# Ethernet_DP.net
KiCad netlist of a schematic drawn in Altium Designer
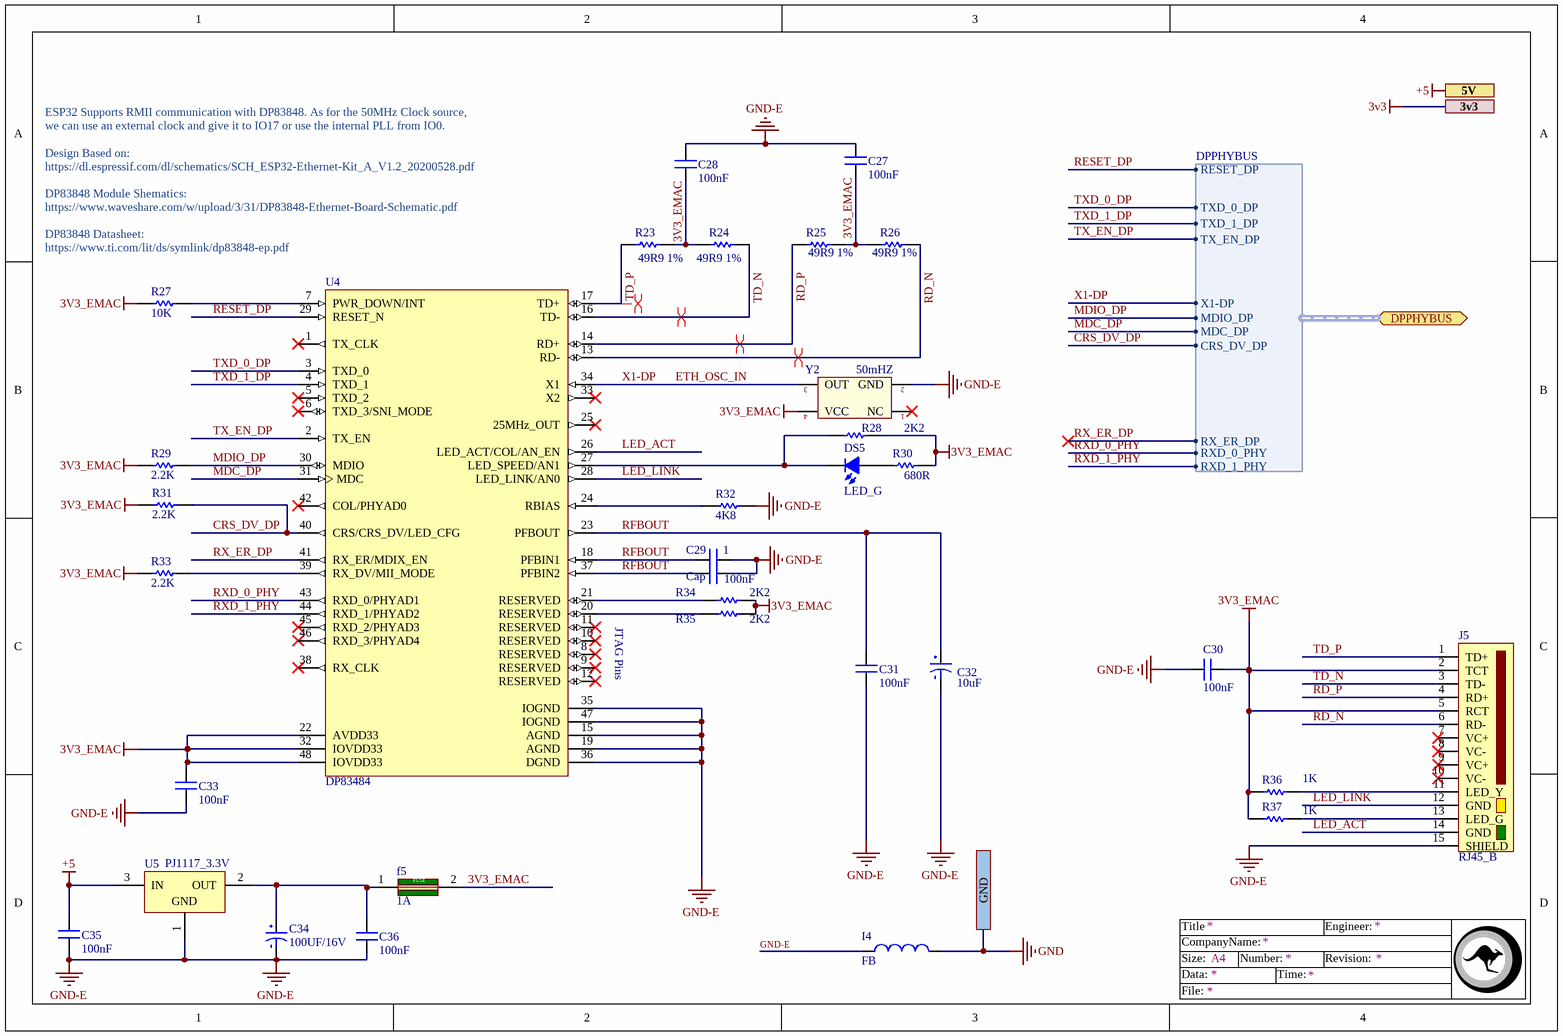
[diagram p0: Ethernet DP.SchDoc]

(export (version "E")
  (design (tool "Eeschema 10.0.6"))
  (components
    (comp (ref "1")
      (value "Cap")
      (footprint "Cap0805")
      (description "Surface mount Capacitor")
      (libsource (lib "PMLIB2020-V3") (part "Cap"))
    )
    (comp (ref "C27")
      (value "100nF")
      (footprint "Cap0805")
      (description "Surface mount Capacitor")
      (libsource (lib "PMLIB2020-V3") (part "Cap"))
    )
    (comp (ref "C28")
      (value "100nF")
      (footprint "Cap0805")
      (description "Surface mount Capacitor")
      (libsource (lib "PMLIB2020-V3") (part "Cap"))
    )
    (comp (ref "C29")
      (value "100nF")
      (footprint "Cap0805")
      (description "Surface mount Capacitor")
      (libsource (lib "PMLIB2020-V3") (part "Cap"))
    )
    (comp (ref "C30")
      (value "100nF")
      (footprint "Cap0805")
      (description "Surface mount Capacitor")
      (libsource (lib "PMLIB2020-V3") (part "Cap"))
    )
    (comp (ref "C31")
      (value "100nF")
      (footprint "Cap0805")
      (description "Surface mount Capacitor")
      (libsource (lib "PMLIB2020-V3") (part "Cap"))
    )
    (comp (ref "C32")
      (value "10uF")
      (footprint "CAPMOL_B")
      (description "Polarity")
      (libsource (lib "PMLIB2020-V3") (part "Cap_P"))
    )
    (comp (ref "C33")
      (value "100nF")
      (footprint "Cap0805")
      (description "Surface mount Capacitor")
      (libsource (lib "PMLIB2020-V3") (part "Cap"))
    )
    (comp (ref "C34")
      (value "100UF/16V")
      (footprint "CAPMOL_A")
      (description "Polarity")
      (libsource (lib "PMLIB2020-V3") (part "Cap_P"))
    )
    (comp (ref "C35")
      (value "100nF")
      (footprint "Cap0805")
      (description "Surface mount Capacitor")
      (libsource (lib "PMLIB2020-V3") (part "Cap"))
    )
    (comp (ref "C36")
      (value "100nF")
      (footprint "Cap0805")
      (description "Surface mount Capacitor")
      (libsource (lib "PMLIB2020-V3") (part "Cap"))
    )
    (comp (ref "DS5")
      (value "LED_G")
      (footprint "LED_0805Green")
      (description "LED")
      (libsource (lib "PMLIB2020-V3") (part "LED"))
    )
    (comp (ref "f5")
      (value "1A")
      (footprint "1206")
      (description "Fuse")
      (libsource (lib "PMLIB2020-V3") (part "Fuse"))
    )
    (comp (ref "I4")
      (value "FB")
      (footprint "1206")
      (description "Indicator")
      (libsource (lib "PMLIB2020-V3") (part "Inductor"))
    )
    (comp (ref "J5")
      (value "RJ45_B")
      (footprint "RJ45_B")
      (description "Ethernet Connector")
      (libsource (lib "PMLIB2020-V3") (part "RJ45_B"))
    )
    (comp (ref "R23")
      (value "49R9 1%")
      (footprint "R0805")
      (description "Resistor")
      (libsource (lib "PMLIB2020-V3") (part "Resistor"))
    )
    (comp (ref "R24")
      (value "49R9 1%")
      (footprint "R0805")
      (description "Resistor")
      (libsource (lib "PMLIB2020-V3") (part "Resistor"))
    )
    (comp (ref "R25")
      (value "49R9 1%")
      (footprint "R0805")
      (description "Resistor")
      (libsource (lib "PMLIB2020-V3") (part "Resistor"))
    )
    (comp (ref "R26")
      (value "49R9 1%")
      (footprint "R0805")
      (description "Resistor")
      (libsource (lib "PMLIB2020-V3") (part "Resistor"))
    )
    (comp (ref "R27")
      (value "10K")
      (footprint "R0805")
      (description "Resistor")
      (libsource (lib "PMLIB2020-V3") (part "Resistor"))
    )
    (comp (ref "R28")
      (value "2K2")
      (footprint "R0805")
      (description "Resistor")
      (libsource (lib "PMLIB2020-V3") (part "Resistor"))
    )
    (comp (ref "R29")
      (value "2.2K")
      (footprint "R0805")
      (description "Resistor")
      (libsource (lib "PMLIB2020-V3") (part "Resistor"))
    )
    (comp (ref "R30")
      (value "680R")
      (footprint "R0805")
      (description "Resistor")
      (libsource (lib "PMLIB2020-V3") (part "Resistor"))
    )
    (comp (ref "R31")
      (value "2.2K")
      (footprint "R0805")
      (description "Resistor")
      (libsource (lib "PMLIB2020-V3") (part "Resistor"))
    )
    (comp (ref "R32")
      (value "4K8")
      (footprint "R0805")
      (description "Resistor")
      (libsource (lib "PMLIB2020-V3") (part "Resistor"))
    )
    (comp (ref "R33")
      (value "2.2K")
      (footprint "R0805")
      (description "Resistor")
      (libsource (lib "PMLIB2020-V3") (part "Resistor"))
    )
    (comp (ref "R34")
      (value "2K2")
      (footprint "R0805")
      (description "Resistor")
      (libsource (lib "PMLIB2020-V3") (part "Resistor"))
    )
    (comp (ref "R35")
      (value "2K2")
      (footprint "R0805")
      (description "Resistor")
      (libsource (lib "PMLIB2020-V3") (part "Resistor"))
    )
    (comp (ref "R36")
      (value "1K")
      (footprint "R0805")
      (description "Resistor")
      (libsource (lib "PMLIB2020-V3") (part "Resistor"))
    )
    (comp (ref "R37")
      (value "1K")
      (footprint "R0805")
      (description "Resistor")
      (libsource (lib "PMLIB2020-V3") (part "Resistor"))
    )
    (comp (ref "U4")
      (value "DP83484")
      (footprint "DP83484")
      (description "Ethernet PHY")
      (libsource (lib "PMLIB2020-V3") (part "DP83484"))
    )
    (comp (ref "U5")
      (value "PJ1117_3.3V")
      (footprint "PJ1117s")
      (description "Regulator")
      (libsource (lib "PMLIB2020-V3") (part "PJ1117_3.3V"))
    )
    (comp (ref "Y2")
      (value "50mHZ")
      (footprint "Crystall 50Mhz")
      (description "Oscillator")
      (libsource (lib "PMLIB2020-V3") (part "Oscillator"))
    )
  )
  (nets
    (net (code "2") (name "+5") (class "Default")
      (node (ref "C35") (pin "2") (pinfunction "2_2") (pintype "passive"))
      (node (ref "U5") (pin "3") (pinfunction "IN_3") (pintype "power_in"))
    )
    (net (code "3") (name "/CRS_DV_DP") (class "Default")
      (node (ref "R31") (pin "1") (pinfunction "1_1") (pintype "passive"))
      (node (ref "U4") (pin "40") (pinfunction "CRS/CRS_DV/LED_CFG_40") (pintype "output"))
    )
    (net (code "4") (name "/ETH_OSC_IN") (class "Default")
      (node (ref "U4") (pin "34") (pinfunction "X1_34") (pintype "input"))
      (node (ref "Y2") (pin "3") (pinfunction "OUT_3") (pintype "passive"))
    )
    (net (code "5") (name "/LED_ACT") (class "Default")
      (node (ref "J5") (pin "14") (pinfunction "GND_14") (pintype "passive"))
      (node (ref "U4") (pin "26") (pinfunction "LED_ACT/COL/AN_EN_26") (pintype "output"))
    )
    (net (code "6") (name "/LED_LINK") (class "Default")
      (node (ref "J5") (pin "12") (pinfunction "GND_12") (pintype "passive"))
      (node (ref "U4") (pin "28") (pinfunction "LED_LINK/AN0_28") (pintype "output"))
    )
    (net (code "7") (name "/MDC_DP") (class "Default")
      (node (ref "U4") (pin "31") (pinfunction "MDC_31") (pintype "input"))
    )
    (net (code "8") (name "/MDIO_DP") (class "Default")
      (node (ref "R29") (pin "1") (pinfunction "1_1") (pintype "passive"))
      (node (ref "U4") (pin "30") (pinfunction "MDIO_30") (pintype "bidirectional"))
    )
    (net (code "9") (name "/RD_N") (class "Default")
      (node (ref "J5") (pin "6") (pinfunction "RD-_6") (pintype "passive"))
      (node (ref "R26") (pin "1") (pinfunction "1_1") (pintype "passive"))
      (node (ref "U4") (pin "13") (pinfunction "RD-_13") (pintype "bidirectional"))
    )
    (net (code "10") (name "/RD_P") (class "Default")
      (node (ref "J5") (pin "4") (pinfunction "RD+_4") (pintype "passive"))
      (node (ref "R25") (pin "2") (pinfunction "2_2") (pintype "passive"))
      (node (ref "U4") (pin "14") (pinfunction "RD+_14") (pintype "bidirectional"))
    )
    (net (code "11") (name "/RESET_DP") (class "Default")
      (node (ref "U4") (pin "29") (pinfunction "RESET_N_29") (pintype "input"))
    )
    (net (code "12") (name "/RFBOUT") (class "Default")
      (node (ref "1") (pin "1") (pinfunction "1_1") (pintype "passive"))
      (node (ref "C29") (pin "1") (pinfunction "1_1") (pintype "passive"))
      (node (ref "C31") (pin "2") (pinfunction "2_2") (pintype "passive"))
      (node (ref "C32") (pin "2") (pinfunction "2_2") (pintype "passive"))
      (node (ref "U4") (pin "18") (pinfunction "PFBIN1_18") (pintype "input"))
      (node (ref "U4") (pin "23") (pinfunction "PFBOUT_23") (pintype "output"))
      (node (ref "U4") (pin "37") (pinfunction "PFBIN2_37") (pintype "input"))
    )
    (net (code "13") (name "/RXD_0_PHY") (class "Default")
      (node (ref "U4") (pin "43") (pinfunction "RXD_0/PHYAD1_43") (pintype "output"))
    )
    (net (code "14") (name "/RXD_1_PHY") (class "Default")
      (node (ref "U4") (pin "44") (pinfunction "RXD_1/PHYAD2_44") (pintype "output"))
    )
    (net (code "15") (name "/RX_ER_DP") (class "Default")
      (node (ref "U4") (pin "41") (pinfunction "RX_ER/MDIX_EN_41") (pintype "output"))
    )
    (net (code "16") (name "/TD_N") (class "Default")
      (node (ref "J5") (pin "3") (pinfunction "TD-_3") (pintype "passive"))
      (node (ref "R24") (pin "1") (pinfunction "1_1") (pintype "passive"))
      (node (ref "U4") (pin "16") (pinfunction "TD-_16") (pintype "bidirectional"))
    )
    (net (code "17") (name "/TD_P") (class "Default")
      (node (ref "J5") (pin "1") (pinfunction "TD+_1") (pintype "passive"))
      (node (ref "R23") (pin "2") (pinfunction "2_2") (pintype "passive"))
      (node (ref "U4") (pin "17") (pinfunction "TD+_17") (pintype "bidirectional"))
    )
    (net (code "18") (name "/TXD_0_DP") (class "Default")
      (node (ref "U4") (pin "3") (pinfunction "TXD_0_3") (pintype "input"))
    )
    (net (code "19") (name "/TXD_1_DP") (class "Default")
      (node (ref "U4") (pin "4") (pinfunction "TXD_1_4") (pintype "input"))
    )
    (net (code "20") (name "/TX_EN_DP") (class "Default")
      (node (ref "U4") (pin "2") (pinfunction "TX_EN_2") (pintype "input"))
    )
    (net (code "22") (name "3V3_EMAC") (class "Default")
      (node (ref "C27") (pin "1") (pinfunction "1_1") (pintype "passive"))
      (node (ref "C28") (pin "1") (pinfunction "1_1") (pintype "passive"))
      (node (ref "C30") (pin "2") (pinfunction "2_2") (pintype "passive"))
      (node (ref "C33") (pin "1") (pinfunction "1_1") (pintype "passive"))
      (node (ref "J5") (pin "2") (pinfunction "TCT_2") (pintype "passive"))
      (node (ref "J5") (pin "5") (pinfunction "RCT_5") (pintype "passive"))
      (node (ref "R23") (pin "1") (pinfunction "1_1") (pintype "passive"))
      (node (ref "R24") (pin "2") (pinfunction "2_2") (pintype "passive"))
      (node (ref "R25") (pin "1") (pinfunction "1_1") (pintype "passive"))
      (node (ref "R26") (pin "2") (pinfunction "2_2") (pintype "passive"))
      (node (ref "R27") (pin "2") (pinfunction "2_2") (pintype "passive"))
      (node (ref "R28") (pin "1") (pinfunction "1_1") (pintype "passive"))
      (node (ref "R29") (pin "2") (pinfunction "2_2") (pintype "passive"))
      (node (ref "R30") (pin "1") (pinfunction "1_1") (pintype "passive"))
      (node (ref "R31") (pin "2") (pinfunction "2_2") (pintype "passive"))
      (node (ref "R33") (pin "2") (pinfunction "2_2") (pintype "passive"))
      (node (ref "R34") (pin "1") (pinfunction "1_1") (pintype "passive"))
      (node (ref "R35") (pin "1") (pinfunction "1_1") (pintype "passive"))
      (node (ref "R36") (pin "2") (pinfunction "2_2") (pintype "passive"))
      (node (ref "R37") (pin "2") (pinfunction "2_2") (pintype "passive"))
      (node (ref "U4") (pin "22") (pinfunction "AVDD33_22") (pintype "power_in"))
      (node (ref "U4") (pin "32") (pinfunction "IOVDD33_32") (pintype "power_in"))
      (node (ref "U4") (pin "48") (pinfunction "IOVDD33_48") (pintype "power_in"))
      (node (ref "Y2") (pin "4") (pinfunction "VCC_4") (pintype "passive"))
      (node (ref "f5") (pin "2") (pinfunction "OUT_2") (pintype "passive"))
    )
    (net (code "24") (name "GND") (class "Default")
      (node (ref "I4") (pin "2") (pinfunction "2_2") (pintype "passive"))
    )
    (net (code "25") (name "GND-E") (class "Default")
      (node (ref "1") (pin "2") (pinfunction "2_2") (pintype "passive"))
      (node (ref "C27") (pin "2") (pinfunction "2_2") (pintype "passive"))
      (node (ref "C28") (pin "2") (pinfunction "2_2") (pintype "passive"))
      (node (ref "C29") (pin "2") (pinfunction "2_2") (pintype "passive"))
      (node (ref "C30") (pin "1") (pinfunction "1_1") (pintype "passive"))
      (node (ref "C31") (pin "1") (pinfunction "1_1") (pintype "passive"))
      (node (ref "C32") (pin "1") (pinfunction "1_1") (pintype "passive"))
      (node (ref "C33") (pin "2") (pinfunction "2_2") (pintype "passive"))
      (node (ref "C34") (pin "1") (pinfunction "1_1") (pintype "passive"))
      (node (ref "C35") (pin "1") (pinfunction "1_1") (pintype "passive"))
      (node (ref "C36") (pin "1") (pinfunction "1_1") (pintype "passive"))
      (node (ref "I4") (pin "1") (pinfunction "1_1") (pintype "passive"))
      (node (ref "J5") (pin "15") (pinfunction "SHIELD_15") (pintype "passive"))
      (node (ref "R32") (pin "1") (pinfunction "1_1") (pintype "passive"))
      (node (ref "U4") (pin "15") (pinfunction "AGND_15") (pintype "power_in"))
      (node (ref "U4") (pin "19") (pinfunction "AGND_19") (pintype "power_in"))
      (node (ref "U4") (pin "35") (pinfunction "IOGND_35") (pintype "power_in"))
      (node (ref "U4") (pin "36") (pinfunction "DGND_36") (pintype "power_in"))
      (node (ref "U4") (pin "47") (pinfunction "IOGND_47") (pintype "power_in"))
      (node (ref "U5") (pin "1") (pinfunction "GND_1") (pintype "power_in"))
      (node (ref "Y2") (pin "2") (pinfunction "GND_2") (pintype "passive"))
    )
    (net (code "26") (name "Net-(DS5-PadA)") (class "Default")
      (node (ref "DS5") (pin "A") (pinfunction "A_A") (pintype "passive"))
      (node (ref "R30") (pin "2") (pinfunction "2_2") (pintype "passive"))
    )
    (net (code "27") (name "Net-(J5-LED_G)") (class "Default")
      (node (ref "J5") (pin "13") (pinfunction "LED_G_13") (pintype "passive"))
      (node (ref "R37") (pin "1") (pinfunction "1_1") (pintype "passive"))
    )
    (net (code "28") (name "Net-(J5-LED_Y)") (class "Default")
      (node (ref "J5") (pin "11") (pinfunction "LED_Y_11") (pintype "passive"))
      (node (ref "R36") (pin "1") (pinfunction "1_1") (pintype "passive"))
    )
    (net (code "29") (name "Net-(R34-Pad2)") (class "Default")
      (node (ref "R34") (pin "2") (pinfunction "2_2") (pintype "passive"))
      (node (ref "U4") (pin "21") (pinfunction "RESERVED_21") (pintype "bidirectional"))
    )
    (net (code "30") (name "Net-(R35-Pad2)") (class "Default")
      (node (ref "R35") (pin "2") (pinfunction "2_2") (pintype "passive"))
      (node (ref "U4") (pin "20") (pinfunction "RESERVED_20") (pintype "bidirectional"))
    )
    (net (code "31") (name "Net-(U4-LED_SPEED{slash}AN1)") (class "Default")
      (node (ref "DS5") (pin "K") (pinfunction "K_K") (pintype "passive"))
      (node (ref "R28") (pin "2") (pinfunction "2_2") (pintype "passive"))
      (node (ref "U4") (pin "27") (pinfunction "LED_SPEED/AN1_27") (pintype "output"))
    )
    (net (code "32") (name "Net-(U4-PWR_DOWN{slash}INT)") (class "Default")
      (node (ref "R27") (pin "1") (pinfunction "1_1") (pintype "passive"))
      (node (ref "U4") (pin "7") (pinfunction "PWR_DOWN/INT_7") (pintype "input"))
    )
    (net (code "33") (name "Net-(U4-RBIAS)") (class "Default")
      (node (ref "R32") (pin "2") (pinfunction "2_2") (pintype "passive"))
      (node (ref "U4") (pin "24") (pinfunction "RBIAS_24") (pintype "input"))
    )
    (net (code "34") (name "Net-(U4-RX_DV{slash}MII_MODE)") (class "Default")
      (node (ref "R33") (pin "1") (pinfunction "1_1") (pintype "passive"))
      (node (ref "U4") (pin "39") (pinfunction "RX_DV/MII_MODE_39") (pintype "output"))
    )
    (net (code "35") (name "Net-(U5-OUT)") (class "Default")
      (node (ref "C34") (pin "2") (pinfunction "2_2") (pintype "passive"))
      (node (ref "C36") (pin "2") (pinfunction "2_2") (pintype "passive"))
      (node (ref "U5") (pin "2") (pinfunction "OUT_2") (pintype "power_in"))
      (node (ref "f5") (pin "1") (pinfunction "IN_1") (pintype "passive"))
    )
    (net (code "36") (name "unconnected-(J5-VC+-Pad7)") (class "Default")
      (node (ref "J5") (pin "7") (pinfunction "VC+_7") (pintype "passive+no_connect"))
    )
    (net (code "37") (name "unconnected-(J5-VC+-Pad9)") (class "Default")
      (node (ref "J5") (pin "9") (pinfunction "VC+_9") (pintype "passive+no_connect"))
    )
    (net (code "38") (name "unconnected-(J5-VC--Pad8)") (class "Default")
      (node (ref "J5") (pin "8") (pinfunction "VC-_8") (pintype "passive+no_connect"))
    )
    (net (code "39") (name "unconnected-(J5-VC--Pad10)") (class "Default")
      (node (ref "J5") (pin "10") (pinfunction "VC-_10") (pintype "passive+no_connect"))
    )
    (net (code "40") (name "unconnected-(U4-25MHz_OUT-Pad25)") (class "Default")
      (node (ref "U4") (pin "25") (pinfunction "25MHz_OUT_25") (pintype "output+no_connect"))
    )
    (net (code "41") (name "unconnected-(U4-COL{slash}PHYAD0-Pad42)") (class "Default")
      (node (ref "U4") (pin "42") (pinfunction "COL/PHYAD0_42") (pintype "output+no_connect"))
    )
    (net (code "42") (name "unconnected-(U4-RESERVED-Pad8)") (class "Default")
      (node (ref "U4") (pin "8") (pinfunction "RESERVED_8") (pintype "bidirectional+no_connect"))
    )
    (net (code "43") (name "unconnected-(U4-RESERVED-Pad9)") (class "Default")
      (node (ref "U4") (pin "9") (pinfunction "RESERVED_9") (pintype "bidirectional+no_connect"))
    )
    (net (code "44") (name "unconnected-(U4-RESERVED-Pad10)") (class "Default")
      (node (ref "U4") (pin "10") (pinfunction "RESERVED_10") (pintype "bidirectional+no_connect"))
    )
    (net (code "45") (name "unconnected-(U4-RESERVED-Pad11)") (class "Default")
      (node (ref "U4") (pin "11") (pinfunction "RESERVED_11") (pintype "bidirectional+no_connect"))
    )
    (net (code "46") (name "unconnected-(U4-RESERVED-Pad12)") (class "Default")
      (node (ref "U4") (pin "12") (pinfunction "RESERVED_12") (pintype "bidirectional+no_connect"))
    )
    (net (code "47") (name "unconnected-(U4-RXD_2{slash}PHYAD3-Pad45)") (class "Default")
      (node (ref "U4") (pin "45") (pinfunction "RXD_2/PHYAD3_45") (pintype "output+no_connect"))
    )
    (net (code "48") (name "unconnected-(U4-RXD_3{slash}PHYAD4-Pad46)") (class "Default")
      (node (ref "U4") (pin "46") (pinfunction "RXD_3/PHYAD4_46") (pintype "output+no_connect"))
    )
    (net (code "49") (name "unconnected-(U4-RX_CLK-Pad38)") (class "Default")
      (node (ref "U4") (pin "38") (pinfunction "RX_CLK_38") (pintype "output+no_connect"))
    )
    (net (code "50") (name "unconnected-(U4-TXD_2-Pad5)") (class "Default")
      (node (ref "U4") (pin "5") (pinfunction "TXD_2_5") (pintype "input+no_connect"))
    )
    (net (code "51") (name "unconnected-(U4-TXD_3{slash}SNI_MODE-Pad6)") (class "Default")
      (node (ref "U4") (pin "6") (pinfunction "TXD_3/SNI_MODE_6") (pintype "bidirectional+no_connect"))
    )
    (net (code "52") (name "unconnected-(U4-TX_CLK-Pad1)") (class "Default")
      (node (ref "U4") (pin "1") (pinfunction "TX_CLK_1") (pintype "output+no_connect"))
    )
    (net (code "53") (name "unconnected-(U4-X2-Pad33)") (class "Default")
      (node (ref "U4") (pin "33") (pinfunction "X2_33") (pintype "output+no_connect"))
    )
    (net (code "54") (name "unconnected-(Y2-NC-Pad1)") (class "Default")
      (node (ref "Y2") (pin "1") (pinfunction "NC_1") (pintype "passive+no_connect"))
    )
  )
)
